# Guide_laser.net
KiCad netlist of a schematic drawn in Altium Designer
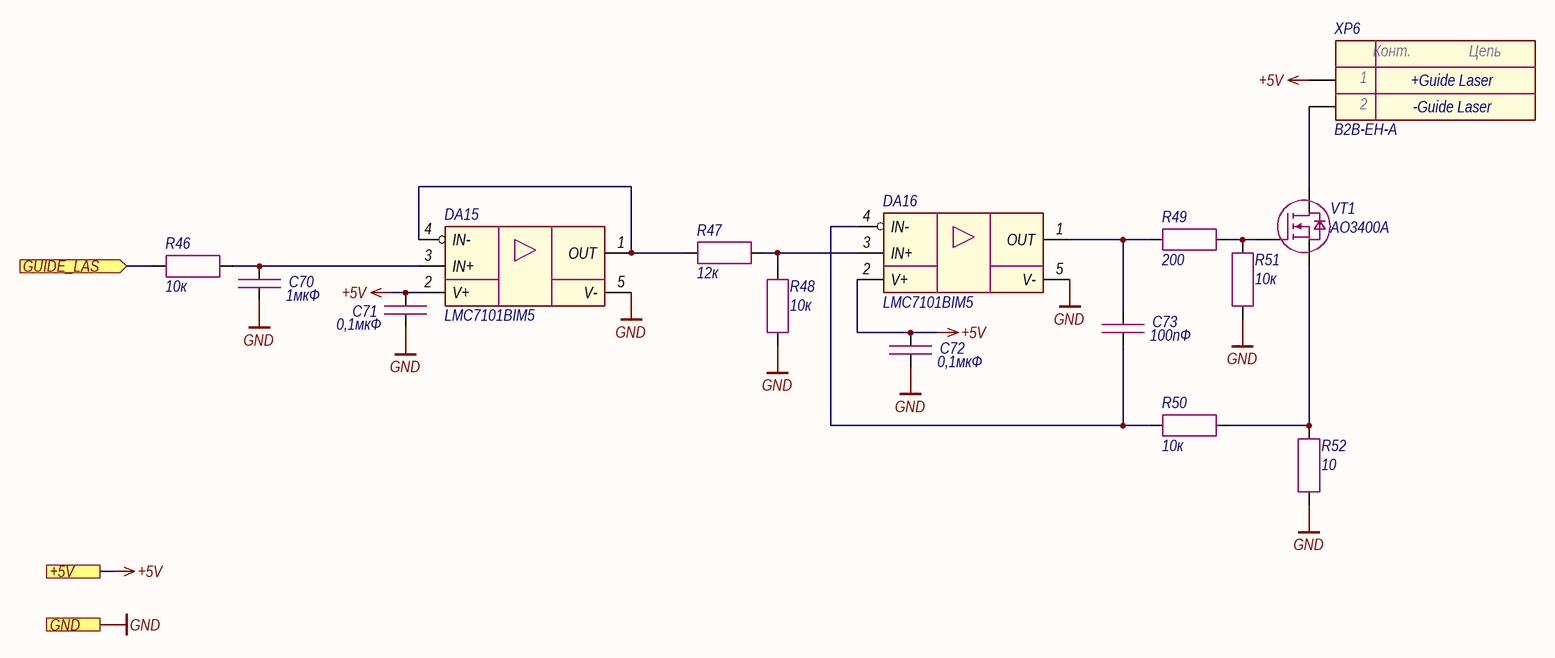
[diagram p0: Guide_laser.SchDoc]

(export (version "E")
  (design (tool "Eeschema 10.0.6"))
  (components
    (comp (ref "C70")
      (value "1мкФ")
      (footprint "Pcb_library:CAP_0603")
      (fields (field (name "MANUFACTURER") "Murata"))
      (libsource (lib "Schem_library") (part "Capacitor"))
    )
    (comp (ref "C71")
      (value "0,1мкФ")
      (footprint "Pcb_library:CAP_0603")
      (fields (field (name "MANUFACTURER") "Murata"))
      (libsource (lib "Schem_library") (part "Capacitor"))
    )
    (comp (ref "C72")
      (value "0,1мкФ")
      (footprint "Pcb_library:CAP_0603")
      (fields (field (name "MANUFACTURER") "Murata"))
      (libsource (lib "Schem_library") (part "Capacitor"))
    )
    (comp (ref "C73")
      (value "100пФ")
      (footprint "Pcb_library:CAP_0603")
      (fields (field (name "MANUFACTURER") "Murata"))
      (libsource (lib "Schem_library") (part "Capacitor"))
    )
    (comp (ref "DA15")
      (value "LMC7101BIM5")
      (footprint "Pcb_library:SOT-23-5")
      (fields (field (name "MANUFACTURER") "Texas Instruments"))
      (libsource (lib "Schem_library") (part "LMC7101"))
    )
    (comp (ref "DA16")
      (value "LMC7101BIM5")
      (footprint "Pcb_library:SOT-23-5")
      (fields (field (name "MANUFACTURER") "Texas Instruments"))
      (libsource (lib "Schem_library") (part "LMC7101"))
    )
    (comp (ref "R46")
      (value "10к")
      (footprint "Pcb_library:RES_0603")
      (fields (field (name "MANUFACTURER") "Yageo"))
      (libsource (lib "Schem_library") (part "Resistor"))
    )
    (comp (ref "R47")
      (value "12к")
      (footprint "Pcb_library:RES_0603")
      (fields (field (name "MANUFACTURER") "Yageo"))
      (libsource (lib "Schem_library") (part "Resistor"))
    )
    (comp (ref "R48")
      (value "10к")
      (footprint "Pcb_library:RES_0603")
      (fields (field (name "MANUFACTURER") "Yageo"))
      (libsource (lib "Schem_library") (part "Resistor"))
    )
    (comp (ref "R49")
      (value "200")
      (footprint "Pcb_library:RES_0603")
      (fields (field (name "MANUFACTURER") "Yageo"))
      (libsource (lib "Schem_library") (part "Resistor"))
    )
    (comp (ref "R50")
      (value "10к")
      (footprint "Pcb_library:RES_0603")
      (fields (field (name "MANUFACTURER") "Yageo"))
      (libsource (lib "Schem_library") (part "Resistor"))
    )
    (comp (ref "R51")
      (value "10к")
      (footprint "Pcb_library:RES_0603")
      (fields (field (name "MANUFACTURER") "Yageo"))
      (libsource (lib "Schem_library") (part "Resistor"))
    )
    (comp (ref "R52")
      (value "10")
      (footprint "Pcb_library:RES_1210")
      (fields (field (name "MANUFACTURER") "Yageo"))
      (libsource (lib "Schem_library") (part "Resistor"))
    )
    (comp (ref "VT1")
      (value "AO3400A")
      (footprint "Pcb_library:SOT-23-3")
      (fields (field (name "MANUFACTURER") "UMW"))
      (libsource (lib "Schem_library") (part "MOSFET N-channel"))
    )
    (comp (ref "XP6")
      (value "B2B-EH-A")
      (footprint "Pcb_library:B2B-EH-A")
      (fields (field (name "MANUFACTURER") "JST"))
      (libsource (lib "Schem_library") (part "Connector-2"))
    )
  )
  (nets
    (net (code "1") (name "+5V") (class "Default")
      (node (ref "C71") (pin "1") (pinfunction "1_1") (pintype "passive"))
      (node (ref "C72") (pin "1") (pinfunction "1_1") (pintype "passive"))
      (node (ref "DA15") (pin "2") (pinfunction "V+_2") (pintype "passive"))
      (node (ref "DA16") (pin "2") (pinfunction "V+_2") (pintype "passive"))
      (node (ref "XP6") (pin "1") (pintype "passive"))
    )
    (net (code "2") (name "/GUIDE_LAS") (class "Default")
      (node (ref "R46") (pin "1") (pinfunction "1_1") (pintype "passive"))
    )
    (net (code "3") (name "GND") (class "Default")
      (node (ref "C70") (pin "2") (pinfunction "2_2") (pintype "passive"))
      (node (ref "C71") (pin "2") (pinfunction "2_2") (pintype "passive"))
      (node (ref "C72") (pin "2") (pinfunction "2_2") (pintype "passive"))
      (node (ref "DA15") (pin "5") (pinfunction "V-_5") (pintype "passive"))
      (node (ref "DA16") (pin "5") (pinfunction "V-_5") (pintype "passive"))
      (node (ref "R48") (pin "2") (pinfunction "2_2") (pintype "passive"))
      (node (ref "R51") (pin "1") (pinfunction "1_1") (pintype "passive"))
      (node (ref "R52") (pin "1") (pinfunction "1_1") (pintype "passive"))
    )
    (net (code "4") (name "Net-(DA15-IN+)") (class "Default")
      (node (ref "C70") (pin "1") (pinfunction "1_1") (pintype "passive"))
      (node (ref "DA15") (pin "3") (pinfunction "IN+_3") (pintype "passive"))
      (node (ref "R46") (pin "2") (pinfunction "2_2") (pintype "passive"))
    )
    (net (code "5") (name "Net-(DA15-IN-)") (class "Default")
      (node (ref "DA15") (pin "1") (pinfunction "OUT_1") (pintype "passive"))
      (node (ref "DA15") (pin "4") (pinfunction "IN-_4") (pintype "passive"))
      (node (ref "R47") (pin "1") (pinfunction "1_1") (pintype "passive"))
    )
    (net (code "6") (name "Net-(DA16-IN+)") (class "Default")
      (node (ref "DA16") (pin "3") (pinfunction "IN+_3") (pintype "passive"))
      (node (ref "R47") (pin "2") (pinfunction "2_2") (pintype "passive"))
      (node (ref "R48") (pin "1") (pinfunction "1_1") (pintype "passive"))
    )
    (net (code "7") (name "Net-(DA16-IN-)") (class "Default")
      (node (ref "C73") (pin "2") (pinfunction "2_2") (pintype "passive"))
      (node (ref "DA16") (pin "4") (pinfunction "IN-_4") (pintype "passive"))
      (node (ref "R50") (pin "1") (pinfunction "1_1") (pintype "passive"))
    )
    (net (code "8") (name "Net-(DA16-OUT)") (class "Default")
      (node (ref "C73") (pin "1") (pinfunction "1_1") (pintype "passive"))
      (node (ref "DA16") (pin "1") (pinfunction "OUT_1") (pintype "passive"))
      (node (ref "R49") (pin "1") (pinfunction "1_1") (pintype "passive"))
    )
    (net (code "9") (name "Net-(VT1-D)") (class "Default")
      (node (ref "VT1") (pin "3") (pinfunction "D_3") (pintype "passive"))
      (node (ref "XP6") (pin "2") (pintype "passive"))
    )
    (net (code "10") (name "Net-(VT1-G)") (class "Default")
      (node (ref "R49") (pin "2") (pinfunction "2_2") (pintype "passive"))
      (node (ref "R51") (pin "2") (pinfunction "2_2") (pintype "passive"))
      (node (ref "VT1") (pin "1") (pinfunction "G_1") (pintype "passive"))
    )
    (net (code "11") (name "Net-(VT1-S)") (class "Default")
      (node (ref "R50") (pin "2") (pinfunction "2_2") (pintype "passive"))
      (node (ref "R52") (pin "2") (pinfunction "2_2") (pintype "passive"))
      (node (ref "VT1") (pin "2") (pinfunction "S_2") (pintype "passive"))
    )
  )
)
